# tkexample-biasing.net
KiCad netlist of a schematic drawn in EAGLE
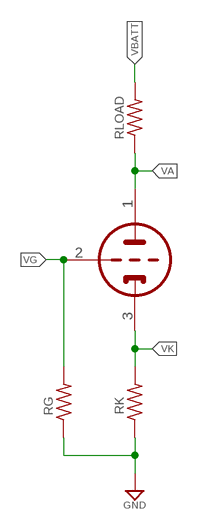
[diagram p0: schematic, sheet 1]

(export (version "E")
  (design (tool "Eeschema 10.0.6"))
  (components
    (comp (ref "RG")
      (value "R-US_R1206")
      (footprint "eagle-import:R1206")
      (libsource (lib "eagle-import") (part "R-US_R1206"))
    )
    (comp (ref "RK")
      (value "R-US_R1206")
      (footprint "eagle-import:R1206")
      (libsource (lib "eagle-import") (part "R-US_R1206"))
    )
    (comp (ref "RLOAD")
      (value "R-US_R1206")
      (footprint "eagle-import:R1206")
      (libsource (lib "eagle-import") (part "R-US_R1206"))
    )
    (comp (ref "V1")
      (value "12AX7-P")
      (footprint "eagle-import:NOVAL")
      (libsource (lib "eagle-import") (part "12AX7-P"))
    )
  )
  (nets
    (net (code "1") (name "GND") (class "Default")
      (node (ref "RG") (pin "1") (pinfunction "1_1") (pintype "passive"))
      (node (ref "RK") (pin "1") (pinfunction "1_1") (pintype "passive"))
    )
    (net (code "2") (name "VA") (class "Default")
      (node (ref "RLOAD") (pin "1") (pinfunction "1_1") (pintype "passive"))
      (node (ref "V1") (pin "1") (pinfunction "TA_1") (pintype "passive"))
    )
    (net (code "3") (name "VBATT") (class "Default")
      (node (ref "RLOAD") (pin "2") (pinfunction "2_2") (pintype "passive"))
    )
    (net (code "4") (name "VG") (class "Default")
      (node (ref "RG") (pin "2") (pinfunction "2_2") (pintype "passive"))
      (node (ref "V1") (pin "2") (pinfunction "TG_2") (pintype "passive"))
    )
    (net (code "5") (name "VK") (class "Default")
      (node (ref "RK") (pin "2") (pinfunction "2_2") (pintype "passive"))
      (node (ref "V1") (pin "3") (pinfunction "TK_3") (pintype "passive"))
    )
  )
)
